# uvmeter.net
KiCad netlist of a schematic drawn in EAGLE
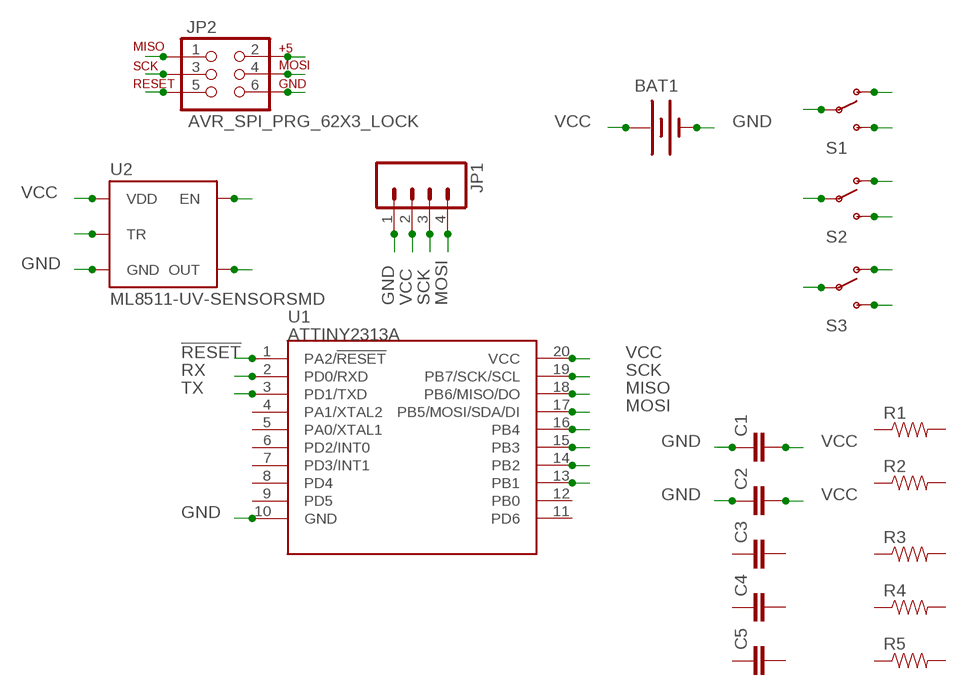
[diagram p0: schematic, sheet 1]

(export (version "E")
  (design (tool "Eeschema 10.0.6"))
  (components
    (comp (ref "BAT1")
      (value "BATTERY20SMD")
      (footprint "eagle-import:BATTCON_20MM")
      (libsource (lib "eagle-import") (part "BATTERY20SMD"))
    )
    (comp (ref "C1")
      (value "CAP0805")
      (footprint "eagle-import:0805")
      (libsource (lib "eagle-import") (part "CAP0805"))
    )
    (comp (ref "C2")
      (value "CAP0805")
      (footprint "eagle-import:0805")
      (libsource (lib "eagle-import") (part "CAP0805"))
    )
    (comp (ref "C3")
      (value "CAP0805")
      (footprint "eagle-import:0805")
      (libsource (lib "eagle-import") (part "CAP0805"))
    )
    (comp (ref "C4")
      (value "CAP0805")
      (footprint "eagle-import:0805")
      (libsource (lib "eagle-import") (part "CAP0805"))
    )
    (comp (ref "C5")
      (value "CAP0805")
      (footprint "eagle-import:0805")
      (libsource (lib "eagle-import") (part "CAP0805"))
    )
    (comp (ref "JP1")
      (value "M04LONGPADS")
      (footprint "eagle-import:1X04_LONGPADS")
      (libsource (lib "eagle-import") (part "M04LONGPADS"))
    )
    (comp (ref "JP2")
      (value "AVR_SPI_PRG_62X3_LOCK")
      (footprint "eagle-import:2X3_LOCK")
      (libsource (lib "eagle-import") (part "AVR_SPI_PRG_62X3_LOCK"))
    )
    (comp (ref "R1")
      (value "RESISTOR0805-RES")
      (footprint "eagle-import:0805")
      (libsource (lib "eagle-import") (part "RESISTOR0805-RES"))
    )
    (comp (ref "R2")
      (value "RESISTOR0805-RES")
      (footprint "eagle-import:0805")
      (libsource (lib "eagle-import") (part "RESISTOR0805-RES"))
    )
    (comp (ref "R3")
      (value "RESISTOR0805-RES")
      (footprint "eagle-import:0805")
      (libsource (lib "eagle-import") (part "RESISTOR0805-RES"))
    )
    (comp (ref "R4")
      (value "RESISTOR0805-RES")
      (footprint "eagle-import:0805")
      (libsource (lib "eagle-import") (part "RESISTOR0805-RES"))
    )
    (comp (ref "R5")
      (value "RESISTOR0805-RES")
      (footprint "eagle-import:0805")
      (libsource (lib "eagle-import") (part "RESISTOR0805-RES"))
    )
    (comp (ref "S1")
      (value "SWITCH-SPDTSMD2")
      (footprint "eagle-import:SWITCH-SPDT-SMD")
      (libsource (lib "eagle-import") (part "SWITCH-SPDTSMD2"))
    )
    (comp (ref "S2")
      (value "SWITCH-SPDTSMD2")
      (footprint "eagle-import:SWITCH-SPDT-SMD")
      (libsource (lib "eagle-import") (part "SWITCH-SPDTSMD2"))
    )
    (comp (ref "S3")
      (value "SWITCH-SPDTSMD2")
      (footprint "eagle-import:SWITCH-SPDT-SMD")
      (libsource (lib "eagle-import") (part "SWITCH-SPDTSMD2"))
    )
    (comp (ref "U1")
      (value "ATTINY2313A")
      (footprint "eagle-import:SOP20W")
      (libsource (lib "eagle-import") (part "ATTINY2313A"))
    )
    (comp (ref "U2")
      (value "ML8511-UV-SENSORSMD")
      (footprint "eagle-import:ML8511")
      (libsource (lib "eagle-import") (part "ML8511-UV-SENSORSMD"))
    )
  )
  (nets
    (net (code "1") (name "/GND") (class "Default")
      (node (ref "BAT1") (pin "2") (pinfunction "-_2") (pintype "power_in"))
      (node (ref "C1") (pin "1") (pinfunction "1_1") (pintype "passive"))
      (node (ref "C2") (pin "1") (pinfunction "1_1") (pintype "passive"))
      (node (ref "JP1") (pin "1") (pinfunction "1_1") (pintype "passive"))
      (node (ref "JP2") (pin "6") (pinfunction "6_6") (pintype "passive"))
      (node (ref "U1") (pin "10") (pinfunction "GND_10") (pintype "bidirectional"))
      (node (ref "U2") (pin "5") (pinfunction "GND_5") (pintype "power_in"))
    )
    (net (code "2") (name "/MISO") (class "Default")
      (node (ref "JP2") (pin "1") (pinfunction "1_1") (pintype "passive"))
      (node (ref "U1") (pin "18") (pinfunction "PB6/MISO/DO_18") (pintype "bidirectional"))
    )
    (net (code "3") (name "/MOSI") (class "Default")
      (node (ref "JP1") (pin "4") (pinfunction "4_4") (pintype "passive"))
      (node (ref "JP2") (pin "4") (pinfunction "4_4") (pintype "passive"))
      (node (ref "U1") (pin "17") (pinfunction "PB5/MOSI/SDA/DI_17") (pintype "bidirectional"))
    )
    (net (code "4") (name "/RX") (class "Default")
      (node (ref "U1") (pin "2") (pinfunction "PD0/RXD_2") (pintype "bidirectional"))
    )
    (net (code "5") (name "/SCK") (class "Default")
      (node (ref "JP1") (pin "3") (pinfunction "3_3") (pintype "passive"))
      (node (ref "JP2") (pin "3") (pinfunction "3_3") (pintype "passive"))
      (node (ref "U1") (pin "19") (pinfunction "PB7/SCK/SCL_19") (pintype "bidirectional"))
    )
    (net (code "6") (name "/TX") (class "Default")
      (node (ref "U1") (pin "3") (pinfunction "PD1/TXD_3") (pintype "bidirectional"))
    )
    (net (code "7") (name "/VCC") (class "Default")
      (node (ref "BAT1") (pin "1") (pinfunction "+_1") (pintype "power_in"))
      (node (ref "C1") (pin "2") (pinfunction "2_2") (pintype "passive"))
      (node (ref "C2") (pin "2") (pinfunction "2_2") (pintype "passive"))
      (node (ref "JP1") (pin "2") (pinfunction "2_2") (pintype "passive"))
      (node (ref "JP2") (pin "2") (pinfunction "2_2") (pintype "passive"))
      (node (ref "U1") (pin "20") (pinfunction "VCC_20") (pintype "bidirectional"))
      (node (ref "U2") (pin "7") (pinfunction "VDD_7") (pintype "power_in"))
    )
    (net (code "8") (name "/~{RESET}") (class "Default")
      (node (ref "JP2") (pin "5") (pinfunction "5_5") (pintype "passive"))
      (node (ref "U1") (pin "1") (pinfunction "PA2/~{RESET}_1") (pintype "bidirectional"))
    )
    (net (code "9") (name "unconnected-(C3-Pad1)") (class "Default")
      (node (ref "C3") (pin "1") (pinfunction "1_1") (pintype "passive"))
    )
    (net (code "10") (name "unconnected-(C3-Pad2)") (class "Default")
      (node (ref "C3") (pin "2") (pinfunction "2_2") (pintype "passive"))
    )
    (net (code "11") (name "unconnected-(C4-Pad1)") (class "Default")
      (node (ref "C4") (pin "1") (pinfunction "1_1") (pintype "passive"))
    )
    (net (code "12") (name "unconnected-(C4-Pad2)") (class "Default")
      (node (ref "C4") (pin "2") (pinfunction "2_2") (pintype "passive"))
    )
    (net (code "13") (name "unconnected-(C5-Pad1)") (class "Default")
      (node (ref "C5") (pin "1") (pinfunction "1_1") (pintype "passive"))
    )
    (net (code "14") (name "unconnected-(C5-Pad2)") (class "Default")
      (node (ref "C5") (pin "2") (pinfunction "2_2") (pintype "passive"))
    )
    (net (code "15") (name "unconnected-(R1-Pad1)") (class "Default")
      (node (ref "R1") (pin "1") (pinfunction "1_1") (pintype "passive"))
    )
    (net (code "16") (name "unconnected-(R1-Pad2)") (class "Default")
      (node (ref "R1") (pin "2") (pinfunction "2_2") (pintype "passive"))
    )
    (net (code "17") (name "unconnected-(R2-Pad1)") (class "Default")
      (node (ref "R2") (pin "1") (pinfunction "1_1") (pintype "passive"))
    )
    (net (code "18") (name "unconnected-(R2-Pad2)") (class "Default")
      (node (ref "R2") (pin "2") (pinfunction "2_2") (pintype "passive"))
    )
    (net (code "19") (name "unconnected-(R3-Pad1)") (class "Default")
      (node (ref "R3") (pin "1") (pinfunction "1_1") (pintype "passive"))
    )
    (net (code "20") (name "unconnected-(R3-Pad2)") (class "Default")
      (node (ref "R3") (pin "2") (pinfunction "2_2") (pintype "passive"))
    )
    (net (code "21") (name "unconnected-(R4-Pad1)") (class "Default")
      (node (ref "R4") (pin "1") (pinfunction "1_1") (pintype "passive"))
    )
    (net (code "22") (name "unconnected-(R4-Pad2)") (class "Default")
      (node (ref "R4") (pin "2") (pinfunction "2_2") (pintype "passive"))
    )
    (net (code "23") (name "unconnected-(R5-Pad1)") (class "Default")
      (node (ref "R5") (pin "1") (pinfunction "1_1") (pintype "passive"))
    )
    (net (code "24") (name "unconnected-(R5-Pad2)") (class "Default")
      (node (ref "R5") (pin "2") (pinfunction "2_2") (pintype "passive"))
    )
    (net (code "25") (name "unconnected-(S1-O-Pad1)") (class "Default")
      (node (ref "S1") (pin "1") (pinfunction "O_1") (pintype "passive"))
    )
    (net (code "26") (name "unconnected-(S1-P-Pad2)") (class "Default")
      (node (ref "S1") (pin "2") (pinfunction "P_2") (pintype "passive"))
    )
    (net (code "27") (name "unconnected-(S1-S-Pad3)") (class "Default")
      (node (ref "S1") (pin "3") (pinfunction "S_3") (pintype "passive"))
    )
    (net (code "28") (name "unconnected-(S2-O-Pad1)") (class "Default")
      (node (ref "S2") (pin "1") (pinfunction "O_1") (pintype "passive"))
    )
    (net (code "29") (name "unconnected-(S2-P-Pad2)") (class "Default")
      (node (ref "S2") (pin "2") (pinfunction "P_2") (pintype "passive"))
    )
    (net (code "30") (name "unconnected-(S2-S-Pad3)") (class "Default")
      (node (ref "S2") (pin "3") (pinfunction "S_3") (pintype "passive"))
    )
    (net (code "31") (name "unconnected-(S3-O-Pad1)") (class "Default")
      (node (ref "S3") (pin "1") (pinfunction "O_1") (pintype "passive"))
    )
    (net (code "32") (name "unconnected-(S3-P-Pad2)") (class "Default")
      (node (ref "S3") (pin "2") (pinfunction "P_2") (pintype "passive"))
    )
    (net (code "33") (name "unconnected-(S3-S-Pad3)") (class "Default")
      (node (ref "S3") (pin "3") (pinfunction "S_3") (pintype "passive"))
    )
    (net (code "34") (name "unconnected-(U1-PA0{slash}XTAL1-Pad5)") (class "Default")
      (node (ref "U1") (pin "5") (pinfunction "PA0/XTAL1_5") (pintype "bidirectional"))
    )
    (net (code "35") (name "unconnected-(U1-PA1{slash}XTAL2-Pad4)") (class "Default")
      (node (ref "U1") (pin "4") (pinfunction "PA1/XTAL2_4") (pintype "bidirectional"))
    )
    (net (code "36") (name "unconnected-(U1-PB0-Pad12)") (class "Default")
      (node (ref "U1") (pin "12") (pinfunction "PB0_12") (pintype "bidirectional"))
    )
    (net (code "37") (name "unconnected-(U1-PB1-Pad13)") (class "Default")
      (node (ref "U1") (pin "13") (pinfunction "PB1_13") (pintype "bidirectional"))
    )
    (net (code "38") (name "unconnected-(U1-PB2-Pad14)") (class "Default")
      (node (ref "U1") (pin "14") (pinfunction "PB2_14") (pintype "bidirectional"))
    )
    (net (code "39") (name "unconnected-(U1-PB3-Pad15)") (class "Default")
      (node (ref "U1") (pin "15") (pinfunction "PB3_15") (pintype "bidirectional"))
    )
    (net (code "40") (name "unconnected-(U1-PB4-Pad16)") (class "Default")
      (node (ref "U1") (pin "16") (pinfunction "PB4_16") (pintype "bidirectional"))
    )
    (net (code "41") (name "unconnected-(U1-PD2{slash}INT0-Pad6)") (class "Default")
      (node (ref "U1") (pin "6") (pinfunction "PD2/INT0_6") (pintype "bidirectional"))
    )
    (net (code "42") (name "unconnected-(U1-PD3{slash}INT1-Pad7)") (class "Default")
      (node (ref "U1") (pin "7") (pinfunction "PD3/INT1_7") (pintype "bidirectional"))
    )
    (net (code "43") (name "unconnected-(U1-PD4-Pad8)") (class "Default")
      (node (ref "U1") (pin "8") (pinfunction "PD4_8") (pintype "bidirectional"))
    )
    (net (code "44") (name "unconnected-(U1-PD5-Pad9)") (class "Default")
      (node (ref "U1") (pin "9") (pinfunction "PD5_9") (pintype "bidirectional"))
    )
    (net (code "45") (name "unconnected-(U1-PD6-Pad11)") (class "Default")
      (node (ref "U1") (pin "11") (pinfunction "PD6_11") (pintype "bidirectional"))
    )
    (net (code "46") (name "unconnected-(U2-EN-Pad4)") (class "Default")
      (node (ref "U2") (pin "4") (pinfunction "EN_4") (pintype "input"))
    )
    (net (code "47") (name "unconnected-(U2-OUT-Pad8)") (class "Default")
      (node (ref "U2") (pin "8") (pinfunction "OUT_8") (pintype "output"))
    )
    (net (code "48") (name "unconnected-(U2-TR-Pad10)") (class "Default")
      (node (ref "U2") (pin "10") (pinfunction "TR_10") (pintype "power_in"))
    )
  )
)
